# DSC-Supply.net
KiCad netlist of a schematic drawn in EAGLE
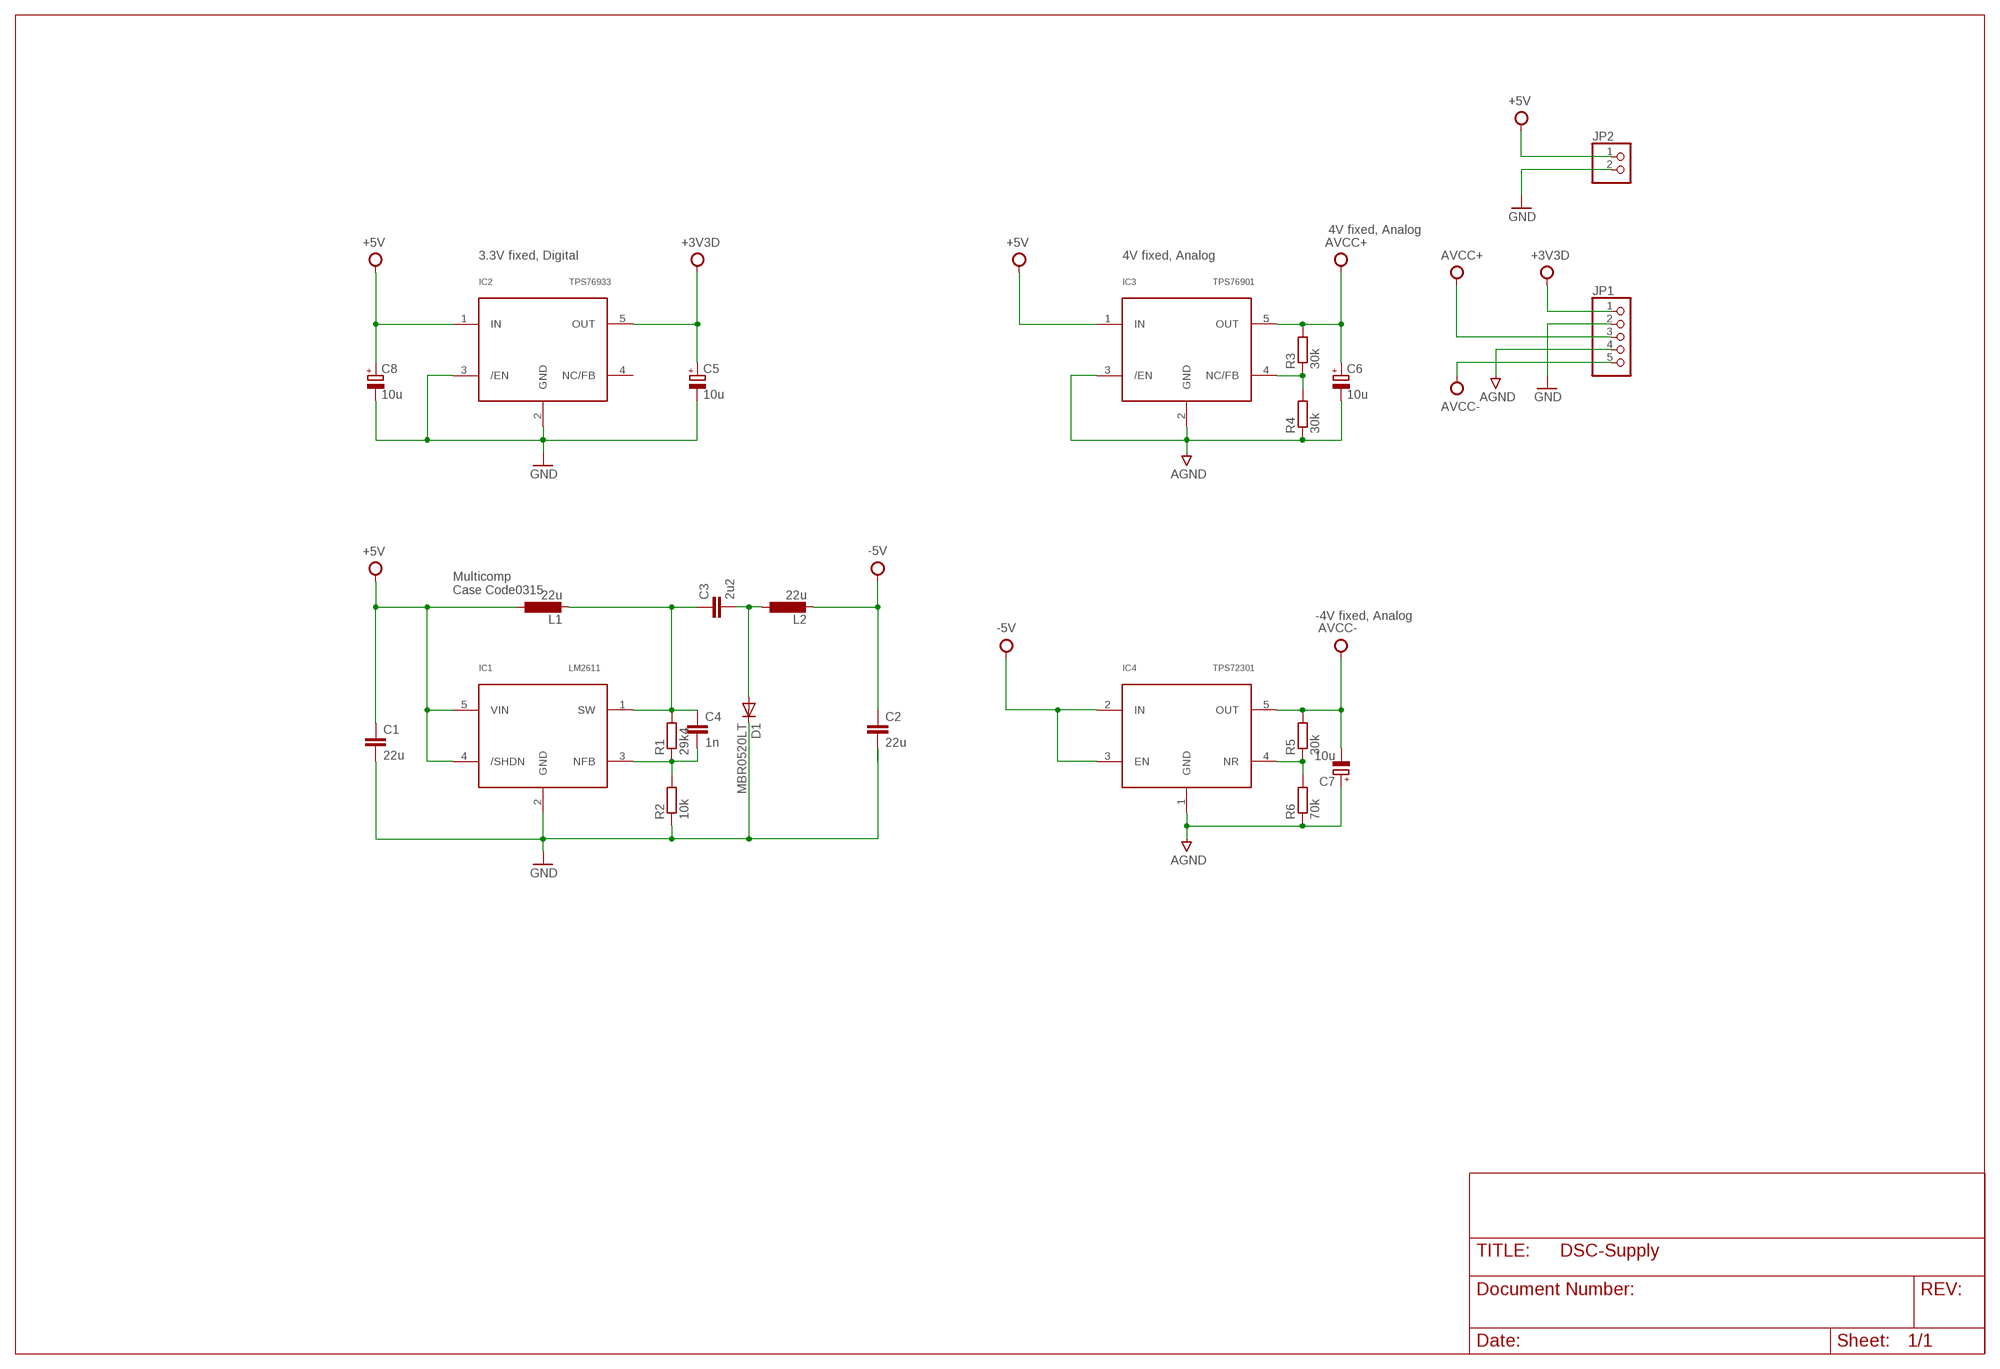
[diagram p0: schematic, sheet 1]

(export (version "E")
  (design (tool "Eeschema 10.0.6"))
  (components
    (comp (ref "C1")
      (value "22u")
      (footprint "eagle-import:C0805")
      (libsource (lib "eagle-import") (part "C-EUC0805"))
    )
    (comp (ref "C2")
      (value "22u")
      (footprint "eagle-import:C0805")
      (libsource (lib "eagle-import") (part "C-EUC0805"))
    )
    (comp (ref "C3")
      (value "2u2")
      (footprint "eagle-import:C0805")
      (libsource (lib "eagle-import") (part "C-EUC0805"))
    )
    (comp (ref "C4")
      (value "1n")
      (footprint "eagle-import:C0805")
      (libsource (lib "eagle-import") (part "C-EUC0805"))
    )
    (comp (ref "C5")
      (value "10u")
      (footprint "eagle-import:153CLV-0405")
      (libsource (lib "eagle-import") (part "CPOL-EU153CLV-0405"))
    )
    (comp (ref "C6")
      (value "10u")
      (footprint "eagle-import:153CLV-0405")
      (libsource (lib "eagle-import") (part "CPOL-EU153CLV-0405"))
    )
    (comp (ref "C7")
      (value "10u")
      (footprint "eagle-import:153CLV-0405")
      (libsource (lib "eagle-import") (part "CPOL-EU153CLV-0405"))
    )
    (comp (ref "C8")
      (value "10u")
      (footprint "eagle-import:153CLV-0405")
      (libsource (lib "eagle-import") (part "CPOL-EU153CLV-0405"))
    )
    (comp (ref "D1")
      (value "MBR0520LT")
      (footprint "eagle-import:SOD123")
      (libsource (lib "eagle-import") (part "MBR0520LT"))
    )
    (comp (ref "IC1")
      (value "LM2611")
      (footprint "eagle-import:SOT23-DBV")
      (libsource (lib "eagle-import") (part "LM2611"))
    )
    (comp (ref "IC2")
      (value "TPS76933")
      (footprint "eagle-import:SOT23-DBV")
      (libsource (lib "eagle-import") (part "TPS769XX"))
    )
    (comp (ref "IC3")
      (value "TPS76901")
      (footprint "eagle-import:SOT23-DBV")
      (libsource (lib "eagle-import") (part "TPS769XX"))
    )
    (comp (ref "IC4")
      (value "TPS72301")
      (footprint "eagle-import:SOT23-DBV")
      (libsource (lib "eagle-import") (part "TPS72301"))
    )
    (comp (ref "JP1")
      (value "PINHD-1X5")
      (footprint "eagle-import:1X05")
      (libsource (lib "eagle-import") (part "PINHD-1X5"))
    )
    (comp (ref "JP2")
      (value "PINHD-1X2")
      (footprint "eagle-import:1X02")
      (libsource (lib "eagle-import") (part "PINHD-1X2"))
    )
    (comp (ref "L1")
      (value "22u")
      (footprint "eagle-import:L0315")
      (libsource (lib "eagle-import") (part "L-EU"))
    )
    (comp (ref "L2")
      (value "22u")
      (footprint "eagle-import:L0315")
      (libsource (lib "eagle-import") (part "L-EU"))
    )
    (comp (ref "R1")
      (value "29k4")
      (footprint "eagle-import:R0805")
      (libsource (lib "eagle-import") (part "R-EU_R0805"))
    )
    (comp (ref "R2")
      (value "10k")
      (footprint "eagle-import:R0805")
      (libsource (lib "eagle-import") (part "R-EU_R0805"))
    )
    (comp (ref "R3")
      (value "30k")
      (footprint "eagle-import:R0805")
      (libsource (lib "eagle-import") (part "R-EU_R0805"))
    )
    (comp (ref "R4")
      (value "30k")
      (footprint "eagle-import:R0805")
      (libsource (lib "eagle-import") (part "R-EU_R0805"))
    )
    (comp (ref "R5")
      (value "30k")
      (footprint "eagle-import:R0805")
      (libsource (lib "eagle-import") (part "R-EU_R0805"))
    )
    (comp (ref "R6")
      (value "70k")
      (footprint "eagle-import:R0805")
      (libsource (lib "eagle-import") (part "R-EU_R0805"))
    )
  )
  (nets
    (net (code "1") (name "+3V3D") (class "Default")
      (node (ref "C5") (pin "+") (pinfunction "+_+") (pintype "passive"))
      (node (ref "IC2") (pin "5") (pinfunction "OUT_5") (pintype "bidirectional"))
      (node (ref "JP1") (pin "1") (pinfunction "1_1") (pintype "passive"))
    )
    (net (code "2") (name "+5V") (class "Default")
      (node (ref "C1") (pin "1") (pinfunction "1_1") (pintype "passive"))
      (node (ref "C8") (pin "+") (pinfunction "+_+") (pintype "passive"))
      (node (ref "IC1") (pin "4") (pinfunction "/SHDN_4") (pintype "input"))
      (node (ref "IC1") (pin "5") (pinfunction "VIN_5") (pintype "input"))
      (node (ref "IC2") (pin "1") (pinfunction "IN_1") (pintype "input"))
      (node (ref "IC3") (pin "1") (pinfunction "IN_1") (pintype "input"))
      (node (ref "JP2") (pin "1") (pinfunction "1_1") (pintype "passive"))
      (node (ref "L1") (pin "1") (pinfunction "1_1") (pintype "passive"))
    )
    (net (code "3") (name "-5V") (class "Default")
      (node (ref "C2") (pin "1") (pinfunction "1_1") (pintype "passive"))
      (node (ref "IC4") (pin "2") (pinfunction "IN_2") (pintype "input"))
      (node (ref "IC4") (pin "3") (pinfunction "EN_3") (pintype "input"))
      (node (ref "L2") (pin "2") (pinfunction "2_2") (pintype "passive"))
    )
    (net (code "4") (name "AGND") (class "Default")
      (node (ref "C6") (pin "-") (pinfunction "-_-") (pintype "passive"))
      (node (ref "C7") (pin "+") (pinfunction "+_+") (pintype "passive"))
      (node (ref "IC3") (pin "2") (pinfunction "GND_2") (pintype "power_in"))
      (node (ref "IC3") (pin "3") (pinfunction "/EN_3") (pintype "input"))
      (node (ref "IC4") (pin "1") (pinfunction "GND_1") (pintype "power_in"))
      (node (ref "JP1") (pin "4") (pinfunction "4_4") (pintype "passive"))
      (node (ref "R4") (pin "1") (pinfunction "1_1") (pintype "passive"))
      (node (ref "R6") (pin "1") (pinfunction "1_1") (pintype "passive"))
    )
    (net (code "5") (name "AVCC+") (class "Default")
      (node (ref "C6") (pin "+") (pinfunction "+_+") (pintype "passive"))
      (node (ref "IC3") (pin "5") (pinfunction "OUT_5") (pintype "bidirectional"))
      (node (ref "JP1") (pin "3") (pinfunction "3_3") (pintype "passive"))
      (node (ref "R3") (pin "2") (pinfunction "2_2") (pintype "passive"))
    )
    (net (code "6") (name "AVCC-") (class "Default")
      (node (ref "C7") (pin "-") (pinfunction "-_-") (pintype "passive"))
      (node (ref "IC4") (pin "5") (pinfunction "OUT_5") (pintype "bidirectional"))
      (node (ref "JP1") (pin "5") (pinfunction "5_5") (pintype "passive"))
      (node (ref "R5") (pin "2") (pinfunction "2_2") (pintype "passive"))
    )
    (net (code "7") (name "GND") (class "Default")
      (node (ref "C1") (pin "2") (pinfunction "2_2") (pintype "passive"))
      (node (ref "C2") (pin "2") (pinfunction "2_2") (pintype "passive"))
      (node (ref "C5") (pin "-") (pinfunction "-_-") (pintype "passive"))
      (node (ref "C8") (pin "-") (pinfunction "-_-") (pintype "passive"))
      (node (ref "D1") (pin "C") (pinfunction "C_C") (pintype "passive"))
      (node (ref "IC1") (pin "2") (pinfunction "GND_2") (pintype "power_in"))
      (node (ref "IC2") (pin "2") (pinfunction "GND_2") (pintype "power_in"))
      (node (ref "IC2") (pin "3") (pinfunction "/EN_3") (pintype "input"))
      (node (ref "JP1") (pin "2") (pinfunction "2_2") (pintype "passive"))
      (node (ref "JP2") (pin "2") (pinfunction "2_2") (pintype "passive"))
      (node (ref "R2") (pin "1") (pinfunction "1_1") (pintype "passive"))
    )
    (net (code "8") (name "Net-(C3-Pad2)") (class "Default")
      (node (ref "C3") (pin "2") (pinfunction "2_2") (pintype "passive"))
      (node (ref "D1") (pin "A") (pinfunction "A_A") (pintype "passive"))
      (node (ref "L2") (pin "1") (pinfunction "1_1") (pintype "passive"))
    )
    (net (code "9") (name "Net-(IC1-NFB)") (class "Default")
      (node (ref "C4") (pin "2") (pinfunction "2_2") (pintype "passive"))
      (node (ref "IC1") (pin "3") (pinfunction "NFB_3") (pintype "input"))
      (node (ref "R1") (pin "1") (pinfunction "1_1") (pintype "passive"))
      (node (ref "R2") (pin "2") (pinfunction "2_2") (pintype "passive"))
    )
    (net (code "10") (name "Net-(IC1-SW)") (class "Default")
      (node (ref "C3") (pin "1") (pinfunction "1_1") (pintype "passive"))
      (node (ref "C4") (pin "1") (pinfunction "1_1") (pintype "passive"))
      (node (ref "IC1") (pin "1") (pinfunction "SW_1") (pintype "bidirectional"))
      (node (ref "L1") (pin "2") (pinfunction "2_2") (pintype "passive"))
      (node (ref "R1") (pin "2") (pinfunction "2_2") (pintype "passive"))
    )
    (net (code "11") (name "Net-(IC3-NC{slash}FB)") (class "Default")
      (node (ref "IC3") (pin "4") (pinfunction "NC/FB_4") (pintype "input"))
      (node (ref "R3") (pin "1") (pinfunction "1_1") (pintype "passive"))
      (node (ref "R4") (pin "2") (pinfunction "2_2") (pintype "passive"))
    )
    (net (code "12") (name "Net-(IC4-NR)") (class "Default")
      (node (ref "IC4") (pin "4") (pinfunction "NR_4") (pintype "input"))
      (node (ref "R5") (pin "1") (pinfunction "1_1") (pintype "passive"))
      (node (ref "R6") (pin "2") (pinfunction "2_2") (pintype "passive"))
    )
    (net (code "13") (name "unconnected-(IC2-NC{slash}FB-Pad4)") (class "Default")
      (node (ref "IC2") (pin "4") (pinfunction "NC/FB_4") (pintype "input"))
    )
  )
)
